# IMU.net
KiCad netlist of a schematic drawn in Altium Designer
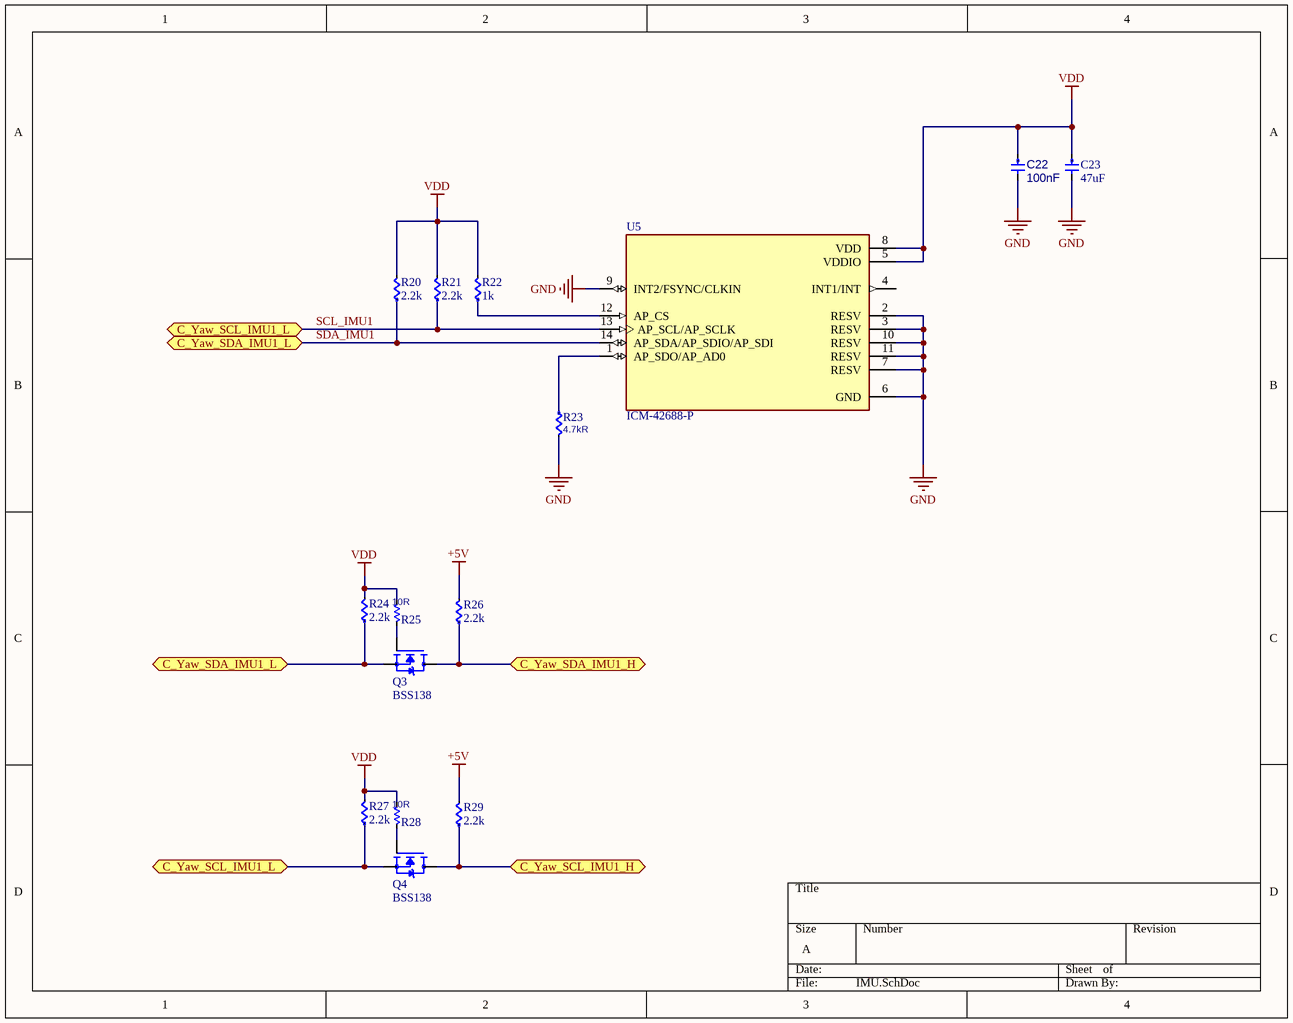
[diagram p0: IMU.SchDoc]

(export (version "E")
  (design (tool "Eeschema 10.0.6"))
  (components
    (comp (ref "C22")
      (value "C0603C104M5RACTU")
      (footprint "CAP0603")
      (description "CAP CER 0.1UF 50V X7R 0603")
      (fields (field (name "TOLERANCE") "20%") (field (name "CAPACITANCE") "100nF"))
      (libsource (lib "rtr") (part "CMP-00691-1"))
    )
    (comp (ref "C23")
      (value "CL21A476MQYNNNE")
      (footprint "CAP0805")
      (description "CAP CER 47UF 6.3V X5R 0805")
      (fields (field (name "TOLERANCE") "20%") (field (name "CAPACITANCE") "47uF"))
      (libsource (lib "rtr") (part "885012107014"))
    )
    (comp (ref "Q3")
      (value "BSS138")
      (footprint "BSS138")
      (description "N-Channel 50 V 220mA (Ta) 350mW (Ta) Surface Mount SOT-23-3")
      (fields (field (name "MF") "onsemi"))
      (libsource (lib "Sbus to Uart") (part "BSS138"))
    )
    (comp (ref "Q4")
      (value "BSS138")
      (footprint "BSS138")
      (description "N-Channel 50 V 220mA (Ta) 350mW (Ta) Surface Mount SOT-23-3")
      (fields (field (name "MF") "onsemi"))
      (libsource (lib "Sbus to Uart") (part "BSS138"))
    )
    (comp (ref "R20")
      (value "2.2k")
      (footprint "RES0603")
      (description "Res Thick Film 0603 2.2K Ohm 1% 0.1W(1/10W) +/-100ppm/C Epoxy Pad SMD T/R")
      (fields
        (field (name "MANUFACTURER") "Yageo Group")
        (field (name "MANUFACTURER PART NUMBER") "RC0603FR-072K2L")
      )
      (libsource (lib "Yaw-Ofil") (part "RC0603FR-072K2L"))
    )
    (comp (ref "R21")
      (value "2.2k")
      (footprint "RES0603")
      (description "Res Thick Film 0603 2.2K Ohm 1% 0.1W(1/10W) +/-100ppm/C Epoxy Pad SMD T/R")
      (fields
        (field (name "MANUFACTURER") "Yageo Group")
        (field (name "MANUFACTURER PART NUMBER") "RC0603FR-072K2L")
      )
      (libsource (lib "Yaw-Ofil") (part "RC0603FR-072K2L"))
    )
    (comp (ref "R22")
      (value "1k")
      (footprint "RES0603")
      (description "Res Thick Film 0603 2.2K Ohm 1% 0.1W(1/10W) +/-100ppm/C Epoxy Pad SMD T/R")
      (fields
        (field (name "MANUFACTURER") "Yageo Group")
        (field (name "MANUFACTURER PART NUMBER") "RC0603FR-072K2L")
      )
      (libsource (lib "Yaw-Ofil") (part "RC0603FR-072K2L"))
    )
    (comp (ref "R23")
      (value "RC0603JR-074K7L")
      (footprint "RES0603")
      (description "RES SMD 4.7K OHM 5% 1/10W 0603")
      (fields (field (name "TOLERANCE") "5%") (field (name "RESISTANCE") "4.7kR"))
      (libsource (lib "rtr") (part "CMP-01404-1"))
    )
    (comp (ref "R24")
      (value "2.2k")
      (footprint "RES0603")
      (description "Res Thick Film 0603 2.2K Ohm 1% 0.1W(1/10W) +/-100ppm/C Epoxy Pad SMD T/R")
      (fields
        (field (name "MANUFACTURER") "Yageo Group")
        (field (name "MANUFACTURER PART NUMBER") "RC0603FR-072K2L")
      )
      (libsource (lib "Yaw-Ofil") (part "RC0603FR-072K2L"))
    )
    (comp (ref "R25")
      (value "10R")
      (footprint "RES0603")
      (description "RES 0805")
      (fields (field (name "MP") "add later") (field (name "Comment") "RES0603"))
      (libsource (lib "RTR") (part "RES0603"))
    )
    (comp (ref "R26")
      (value "2.2k")
      (footprint "RES0603")
      (description "Res Thick Film 0603 2.2K Ohm 1% 0.1W(1/10W) +/-100ppm/C Epoxy Pad SMD T/R")
      (fields
        (field (name "MANUFACTURER") "Yageo Group")
        (field (name "MANUFACTURER PART NUMBER") "RC0603FR-072K2L")
      )
      (libsource (lib "Yaw-Ofil") (part "RC0603FR-072K2L"))
    )
    (comp (ref "R27")
      (value "2.2k")
      (footprint "RES0603")
      (description "Res Thick Film 0603 2.2K Ohm 1% 0.1W(1/10W) +/-100ppm/C Epoxy Pad SMD T/R")
      (fields
        (field (name "MANUFACTURER") "Yageo Group")
        (field (name "MANUFACTURER PART NUMBER") "RC0603FR-072K2L")
      )
      (libsource (lib "Yaw-Ofil") (part "RC0603FR-072K2L"))
    )
    (comp (ref "R28")
      (value "10R")
      (footprint "RES0603")
      (description "RES 0805")
      (fields (field (name "MP") "add later") (field (name "Comment") "RES0603"))
      (libsource (lib "RTR") (part "RES0603"))
    )
    (comp (ref "R29")
      (value "2.2k")
      (footprint "RES0603")
      (description "Res Thick Film 0603 2.2K Ohm 1% 0.1W(1/10W) +/-100ppm/C Epoxy Pad SMD T/R")
      (fields
        (field (name "MANUFACTURER") "Yageo Group")
        (field (name "MANUFACTURER PART NUMBER") "RC0603FR-072K2L")
      )
      (libsource (lib "Yaw-Ofil") (part "RC0603FR-072K2L"))
    )
    (comp (ref "U5")
      (value "ICM-42688-P")
      (footprint "ICM-42688-P")
      (description "Accelerometer, Gyroscope, 6 Axis Sensor Output")
      (libsource (lib "DRV8312DDW") (part "ICM-42688-P"))
    )
  )
  (nets
    (net (code "1") (name "+5V") (class "Default")
      (node (ref "R26") (pin "2") (pinfunction "2_2") (pintype "passive"))
      (node (ref "R29") (pin "2") (pinfunction "2_2") (pintype "passive"))
    )
    (net (code "2") (name "/C_Yaw_SCL_IMU1_H") (class "Default")
      (node (ref "Q4") (pin "3") (pinfunction "D_3") (pintype "passive"))
      (node (ref "R29") (pin "1") (pinfunction "1_1") (pintype "passive"))
    )
    (net (code "3") (name "/C_Yaw_SDA_IMU1_H") (class "Default")
      (node (ref "Q3") (pin "3") (pinfunction "D_3") (pintype "passive"))
      (node (ref "R26") (pin "1") (pinfunction "1_1") (pintype "passive"))
    )
    (net (code "4") (name "/SCL_IMU1") (class "Default")
      (node (ref "Q4") (pin "2") (pinfunction "S_2") (pintype "passive"))
      (node (ref "R21") (pin "1") (pinfunction "1_1") (pintype "passive"))
      (node (ref "R27") (pin "1") (pinfunction "1_1") (pintype "passive"))
      (node (ref "U5") (pin "13") (pinfunction "AP_SCL/AP_SCLK_13") (pintype "input"))
    )
    (net (code "5") (name "/SDA_IMU1") (class "Default")
      (node (ref "Q3") (pin "2") (pinfunction "S_2") (pintype "passive"))
      (node (ref "R20") (pin "1") (pinfunction "1_1") (pintype "passive"))
      (node (ref "R24") (pin "1") (pinfunction "1_1") (pintype "passive"))
      (node (ref "U5") (pin "14") (pinfunction "AP_SDA/AP_SDIO/AP_SDI_14") (pintype "bidirectional"))
    )
    (net (code "6") (name "GND") (class "Default")
      (node (ref "C22") (pin "2") (pinfunction "2_2") (pintype "passive"))
      (node (ref "C23") (pin "2") (pinfunction "2_2") (pintype "passive"))
      (node (ref "R23") (pin "2") (pinfunction "2_2") (pintype "passive"))
      (node (ref "U5") (pin "10") (pinfunction "RESV_10") (pintype "passive"))
      (node (ref "U5") (pin "11") (pinfunction "RESV_11") (pintype "passive"))
      (node (ref "U5") (pin "2") (pinfunction "RESV_2") (pintype "passive"))
      (node (ref "U5") (pin "3") (pinfunction "RESV_3") (pintype "passive"))
      (node (ref "U5") (pin "6") (pinfunction "GND_6") (pintype "power_in"))
      (node (ref "U5") (pin "7") (pinfunction "RESV_7") (pintype "passive"))
      (node (ref "U5") (pin "9") (pinfunction "INT2/FSYNC/CLKIN_9") (pintype "bidirectional"))
    )
    (net (code "7") (name "Net-(Q3-G)") (class "Default")
      (node (ref "Q3") (pin "1") (pinfunction "G_1") (pintype "passive"))
      (node (ref "R25") (pin "2") (pinfunction "2_2") (pintype "passive"))
    )
    (net (code "8") (name "Net-(Q4-G)") (class "Default")
      (node (ref "Q4") (pin "1") (pinfunction "G_1") (pintype "passive"))
      (node (ref "R28") (pin "2") (pinfunction "2_2") (pintype "passive"))
    )
    (net (code "9") (name "Net-(U5-AP_CS)") (class "Default")
      (node (ref "R22") (pin "1") (pinfunction "1_1") (pintype "passive"))
      (node (ref "U5") (pin "12") (pinfunction "AP_CS_12") (pintype "input"))
    )
    (net (code "10") (name "Net-(U5-AP_SDO{slash}AP_AD0)") (class "Default")
      (node (ref "R23") (pin "1") (pinfunction "1_1") (pintype "passive"))
      (node (ref "U5") (pin "1") (pinfunction "AP_SDO/AP_AD0_1") (pintype "bidirectional"))
    )
    (net (code "11") (name "VDD") (class "Default")
      (node (ref "C22") (pin "1") (pinfunction "1_1") (pintype "passive"))
      (node (ref "C23") (pin "1") (pinfunction "1_1") (pintype "passive"))
      (node (ref "R20") (pin "2") (pinfunction "2_2") (pintype "passive"))
      (node (ref "R21") (pin "2") (pinfunction "2_2") (pintype "passive"))
      (node (ref "R22") (pin "2") (pinfunction "2_2") (pintype "passive"))
      (node (ref "R24") (pin "2") (pinfunction "2_2") (pintype "passive"))
      (node (ref "R25") (pin "1") (pinfunction "1_1") (pintype "passive"))
      (node (ref "R27") (pin "2") (pinfunction "2_2") (pintype "passive"))
      (node (ref "R28") (pin "1") (pinfunction "1_1") (pintype "passive"))
      (node (ref "U5") (pin "5") (pinfunction "VDDIO_5") (pintype "power_in"))
      (node (ref "U5") (pin "8") (pinfunction "VDD_8") (pintype "power_in"))
    )
    (net (code "12") (name "unconnected-(U5-INT1{slash}INT-Pad4)") (class "Default")
      (node (ref "U5") (pin "4") (pinfunction "INT1/INT_4") (pintype "output"))
    )
  )
)
